# TSOC_GROVEY_ONE.net
KiCad netlist of a schematic drawn in EAGLE
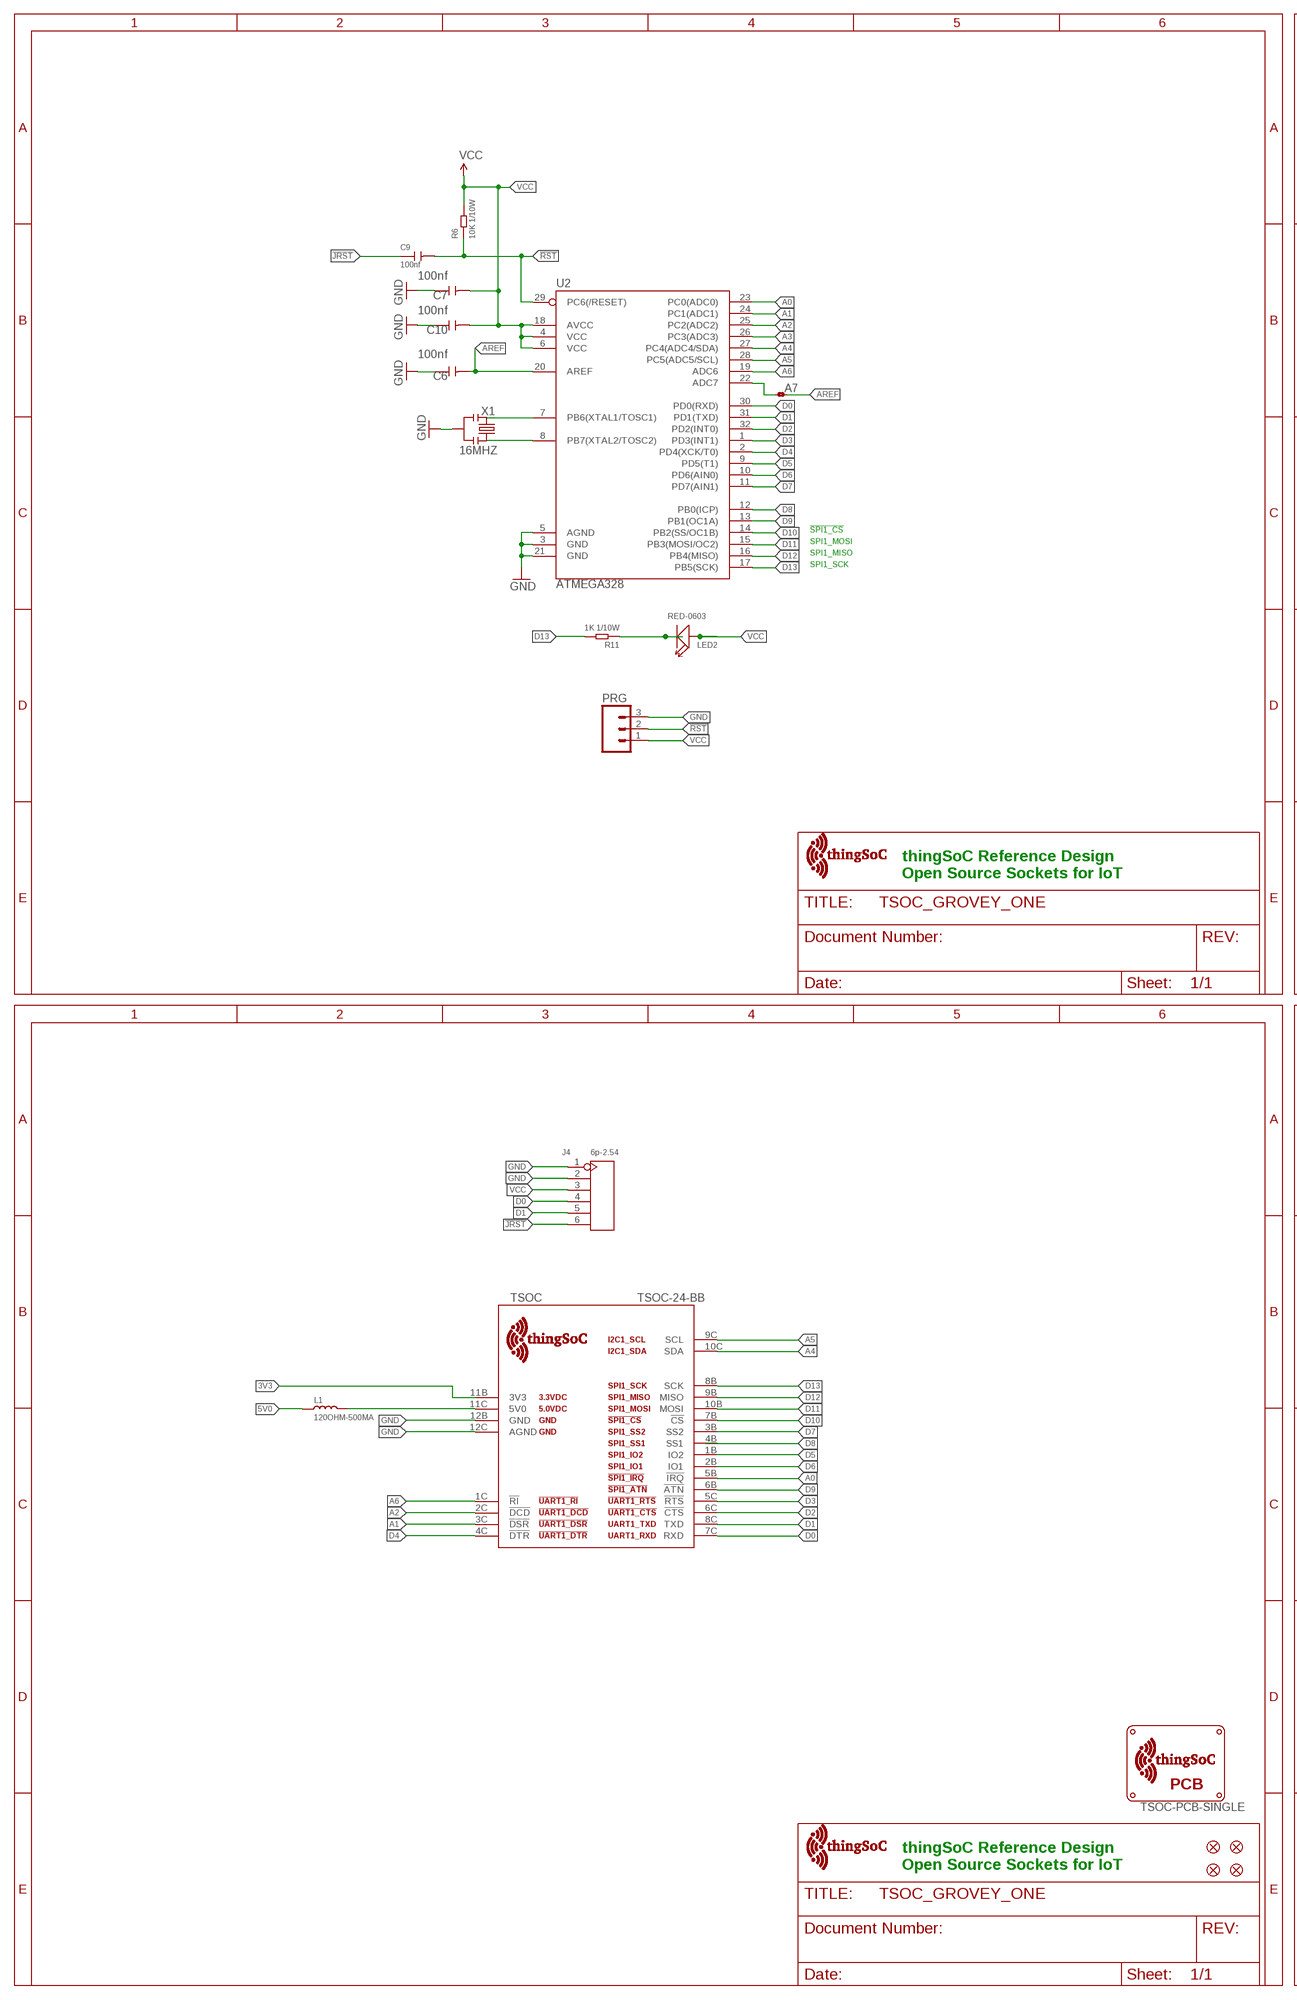
[diagram p0: schematic, sheet 1, part 1 of 2]
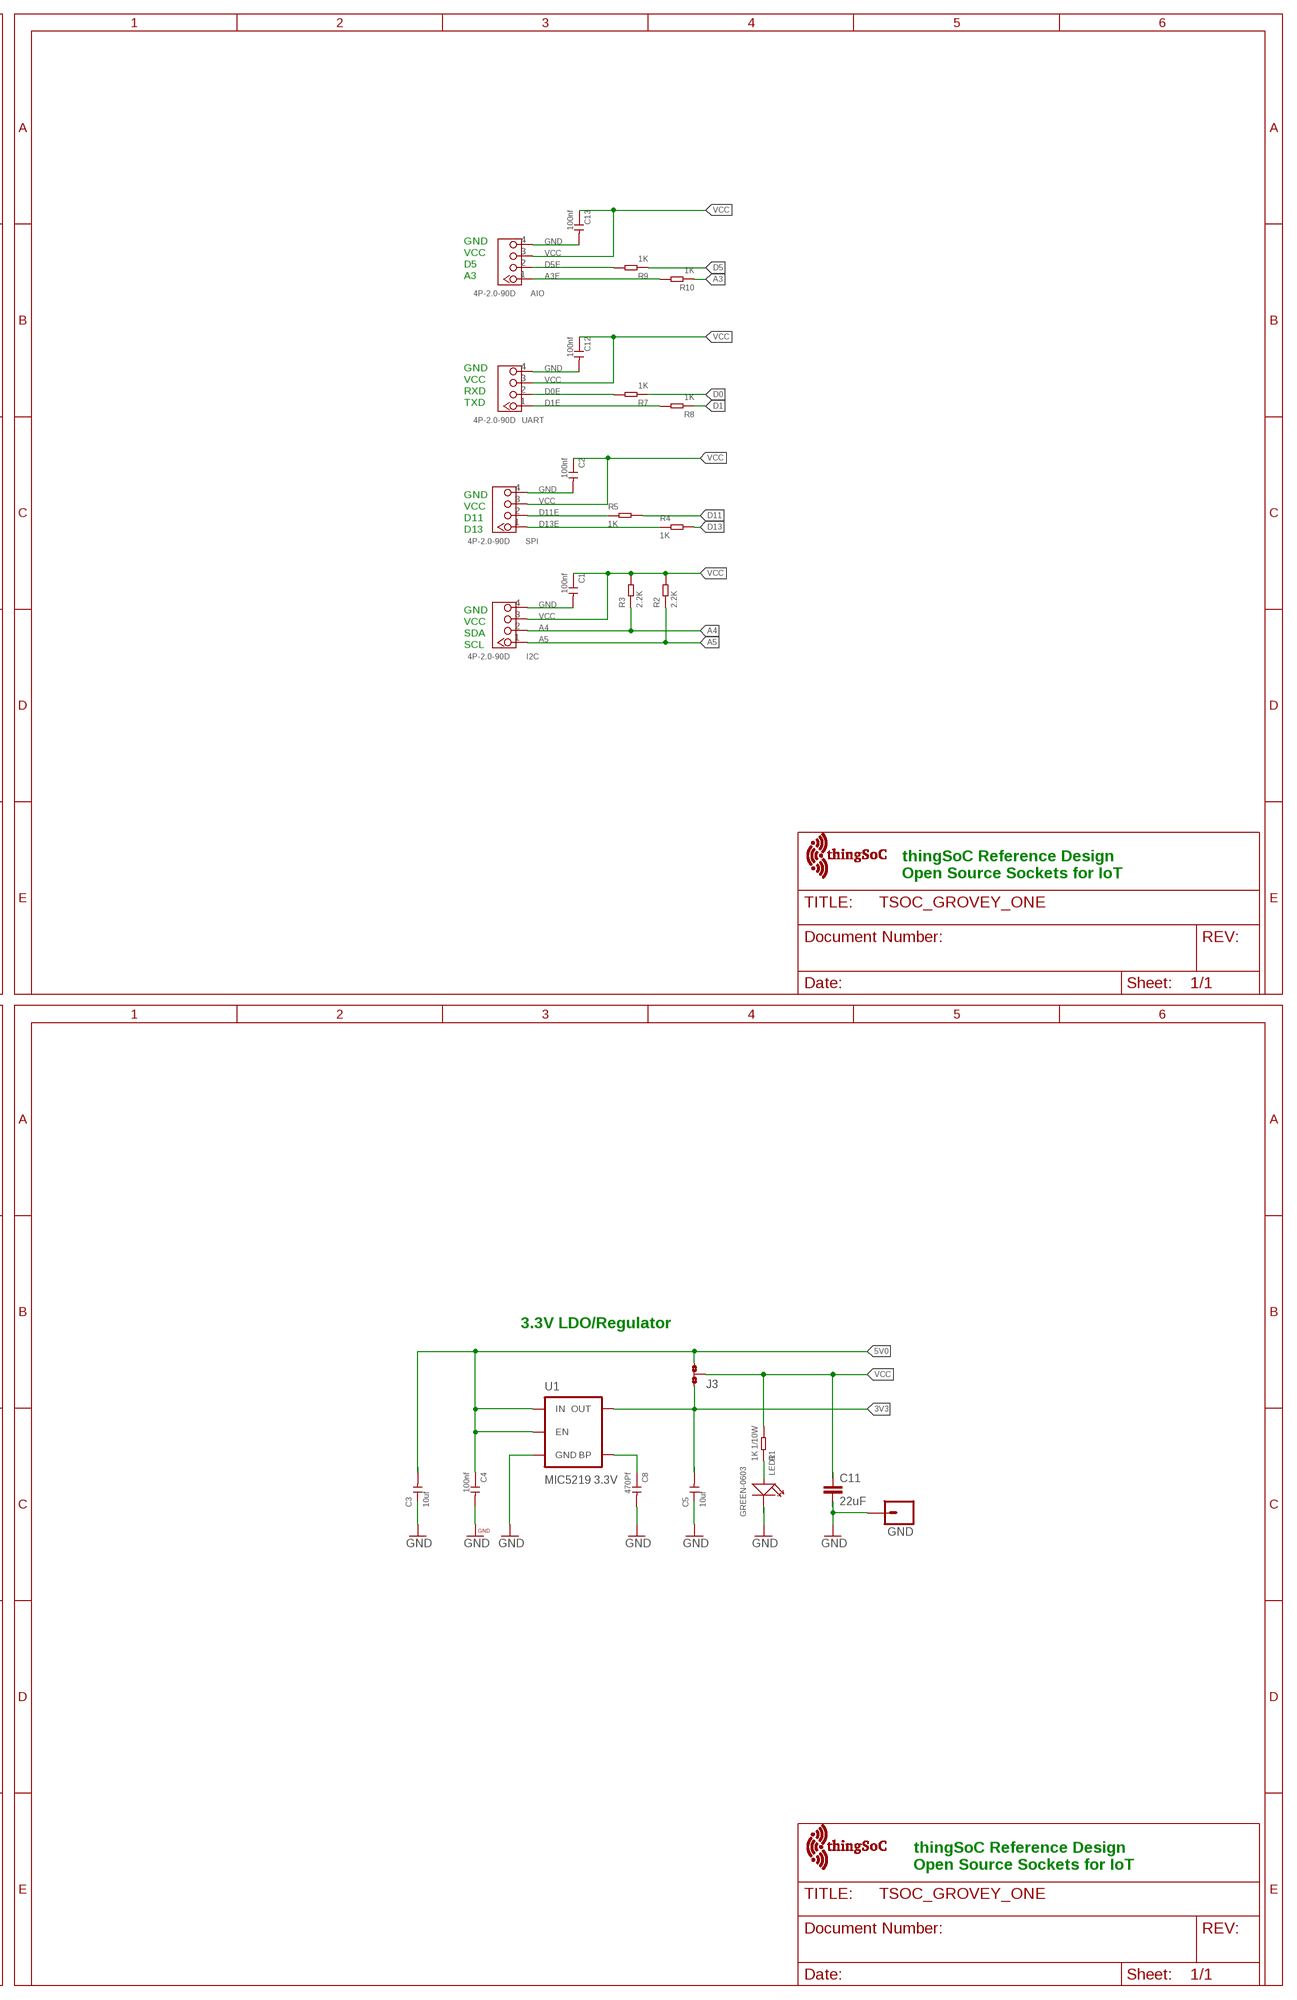
[diagram p1: schematic, sheet 1, part 2 of 2]

(export (version "E")
  (design (tool "Eeschema 10.0.6"))
  (components
    (comp (ref "$$U$1")
      (value "TSOC-PCB-SINGLE")
      (footprint "eagle-import:TSOC-BB-BRD-DIM")
      (libsource (lib "eagle-import") (part "TSOC-PCB-SINGLE"))
    )
    (comp (ref "A7")
      (value "JMP-2-NO")
      (footprint "eagle-import:JMP-2-NO")
      (libsource (lib "eagle-import") (part "JMP-2-NO"))
    )
    (comp (ref "AIO")
      (value "4P-2.0-90D")
      (footprint "eagle-import:HW4-2.0-90D")
      (libsource (lib "eagle-import") (part "GROVE-CONNECTOR-DIP-90D(4P-2.0)"))
    )
    (comp (ref "C1")
      (value "100nf")
      (footprint "eagle-import:C0603")
      (fields (field (name "MPN") "CC0603KRX7R9BB104"))
      (libsource (lib "eagle-import") (part "CERAMIC-100NF-50V-10%-X7R(0603)"))
    )
    (comp (ref "C2")
      (value "100nf")
      (footprint "eagle-import:C0603")
      (fields (field (name "MPN") "CC0603KRX7R9BB104"))
      (libsource (lib "eagle-import") (part "CERAMIC-100NF-50V-10%-X7R(0603)"))
    )
    (comp (ref "C3")
      (value "10uf")
      (footprint "eagle-import:C0603")
      (fields (field (name "MPN") "CC0603KRX5R6BB106"))
      (libsource (lib "eagle-import") (part "CERAMIC-10UF-10V-10%-X5R(0603)"))
    )
    (comp (ref "C4")
      (value "100nf")
      (footprint "eagle-import:C0603")
      (fields (field (name "MPN") "CC0603KRX7R9BB104"))
      (libsource (lib "eagle-import") (part "CERAMIC-100NF-50V-10%-X7R(0603)"))
    )
    (comp (ref "C5")
      (value "10uf")
      (footprint "eagle-import:C0603")
      (fields (field (name "MPN") "CC0603KRX5R6BB106"))
      (libsource (lib "eagle-import") (part "CERAMIC-10UF-10V-10%-X5R(0603)"))
    )
    (comp (ref "C6")
      (value "100nf")
      (footprint "eagle-import:C0603")
      (fields (field (name "MPN") "CC0603KRX7R9BB104"))
      (libsource (lib "eagle-import") (part "CERAMIC-100NF-50V-10%-X7R(0603)"))
    )
    (comp (ref "C7")
      (value "100nf")
      (footprint "eagle-import:C0603")
      (fields (field (name "MPN") "CC0603KRX7R9BB104"))
      (libsource (lib "eagle-import") (part "CERAMIC-100NF-50V-10%-X7R(0603)"))
    )
    (comp (ref "C8")
      (value "470Pf")
      (footprint "eagle-import:C0603")
      (fields (field (name "MPN") "CC0603KRX7R9BB104"))
      (libsource (lib "eagle-import") (part "CERAMIC-100NF-50V-10%-X7R(0603)"))
    )
    (comp (ref "C9")
      (value "100nf")
      (footprint "eagle-import:C0603")
      (fields (field (name "MPN") "CC0603KRX7R9BB104"))
      (libsource (lib "eagle-import") (part "CERAMIC-100NF-50V-10%-X7R(0603)"))
    )
    (comp (ref "C10")
      (value "100nf")
      (footprint "eagle-import:C0603")
      (fields (field (name "MPN") "CC0603KRX7R9BB104"))
      (libsource (lib "eagle-import") (part "CERAMIC-100NF-50V-10%-X7R(0603)"))
    )
    (comp (ref "C11")
      (value "22uF")
      (footprint "eagle-import:EIA-1206")
      (libsource (lib "eagle-import") (part "CAP-1206"))
    )
    (comp (ref "C12")
      (value "100nf")
      (footprint "eagle-import:C0603")
      (fields (field (name "MPN") "CC0603KRX7R9BB104"))
      (libsource (lib "eagle-import") (part "CERAMIC-100NF-50V-10%-X7R(0603)"))
    )
    (comp (ref "C13")
      (value "100nf")
      (footprint "eagle-import:C0603")
      (fields (field (name "MPN") "CC0603KRX7R9BB104"))
      (libsource (lib "eagle-import") (part "CERAMIC-100NF-50V-10%-X7R(0603)"))
    )
    (comp (ref "FID1")
      (value "FIDUCIALUFIDUCIAL")
      (footprint "eagle-import:MICRO-FIDUCIAL")
      (libsource (lib "eagle-import") (part "FIDUCIALUFIDUCIAL"))
    )
    (comp (ref "FID2")
      (value "FIDUCIALUFIDUCIAL")
      (footprint "eagle-import:MICRO-FIDUCIAL")
      (libsource (lib "eagle-import") (part "FIDUCIALUFIDUCIAL"))
    )
    (comp (ref "FID3")
      (value "FIDUCIALUFIDUCIAL")
      (footprint "eagle-import:MICRO-FIDUCIAL")
      (libsource (lib "eagle-import") (part "FIDUCIALUFIDUCIAL"))
    )
    (comp (ref "FID4")
      (value "FIDUCIALUFIDUCIAL")
      (footprint "eagle-import:MICRO-FIDUCIAL")
      (libsource (lib "eagle-import") (part "FIDUCIALUFIDUCIAL"))
    )
    (comp (ref "GND")
      (value "M01PTH")
      (footprint "eagle-import:1X01")
      (libsource (lib "eagle-import") (part "M01PTH"))
    )
    (comp (ref "I2C")
      (value "4P-2.0-90D")
      (footprint "eagle-import:HW4-2.0-90D")
      (libsource (lib "eagle-import") (part "GROVE-CONNECTOR-DIP-90D(4P-2.0)"))
    )
    (comp (ref "J3")
      (value "NO")
      (footprint "eagle-import:JMP-3-NO-PTH-2.54")
      (libsource (lib "eagle-import") (part "JMP-3-NO-PTH"))
    )
    (comp (ref "J4")
      (value "6p-2.54")
      (footprint "eagle-import:H6-2.54")
      (fields (field (name "MPN") "P125-1106A1BS116A1"))
      (libsource (lib "eagle-import") (part "DIP-BLACK-MALE-HEADER(6P-2.54)"))
    )
    (comp (ref "L1")
      (value "120OHM-500MA")
      (footprint "eagle-import:L0603")
      (fields (field (name "MPN") "BLM18AG121SN1D"))
      (libsource (lib "eagle-import") (part "SMD-FERRITE-CHIP-120-OHM-500MA(0603)"))
    )
    (comp (ref "LED1")
      (value "GREEN-0603")
      (footprint "eagle-import:LED-0603")
      (fields (field (name "MPN") "19-217-G7C-AN1P2-3T"))
      (libsource (lib "eagle-import") (part "SMD-LED-CLEAR-GREEN(0603)"))
    )
    (comp (ref "LED2")
      (value "RED-0603")
      (footprint "eagle-import:LED-0603")
      (fields (field (name "MPN") "19-217-G7C-AN1P2-3T"))
      (libsource (lib "eagle-import") (part "SMD-LED-CLEAR-GREEN(0603)"))
    )
    (comp (ref "PRG")
      (value "M03PTH")
      (footprint "eagle-import:1X03")
      (libsource (lib "eagle-import") (part "M03PTH"))
    )
    (comp (ref "R1")
      (value "1K 1/10W")
      (footprint "eagle-import:R0603")
      (fields (field (name "MPN") "RC0603JR-071KL"))
      (libsource (lib "eagle-import") (part "SMD-RES-1K-5%-1/10W(0603)"))
    )
    (comp (ref "R2")
      (value "2.2K")
      (footprint "eagle-import:R0603")
      (fields (field (name "MPN") "RC0603JR-072K2L"))
      (libsource (lib "eagle-import") (part "SMD-RES-2.2K-5%-1/10W(0603)"))
    )
    (comp (ref "R3")
      (value "2.2K")
      (footprint "eagle-import:R0603")
      (fields (field (name "MPN") "RC0603JR-072K2L"))
      (libsource (lib "eagle-import") (part "SMD-RES-2.2K-5%-1/10W(0603)"))
    )
    (comp (ref "R4")
      (value "1K")
      (footprint "eagle-import:R0603")
      (fields (field (name "MPN") "RC0603JR-072K2L"))
      (libsource (lib "eagle-import") (part "SMD-RES-2.2K-5%-1/10W(0603)"))
    )
    (comp (ref "R5")
      (value "1K")
      (footprint "eagle-import:R0603")
      (fields (field (name "MPN") "RC0603JR-072K2L"))
      (libsource (lib "eagle-import") (part "SMD-RES-2.2K-5%-1/10W(0603)"))
    )
    (comp (ref "R6")
      (value "10K 1/10W")
      (footprint "eagle-import:R0603")
      (fields (field (name "MPN") "RC0603JR-0710KL"))
      (libsource (lib "eagle-import") (part "SMD-RES-10K-5%-1/10W(0603)"))
    )
    (comp (ref "R7")
      (value "1K")
      (footprint "eagle-import:R0603")
      (fields (field (name "MPN") "RC0603JR-072K2L"))
      (libsource (lib "eagle-import") (part "SMD-RES-2.2K-5%-1/10W(0603)"))
    )
    (comp (ref "R8")
      (value "1K")
      (footprint "eagle-import:R0603")
      (fields (field (name "MPN") "RC0603JR-072K2L"))
      (libsource (lib "eagle-import") (part "SMD-RES-2.2K-5%-1/10W(0603)"))
    )
    (comp (ref "R9")
      (value "1K")
      (footprint "eagle-import:R0603")
      (fields (field (name "MPN") "RC0603JR-072K2L"))
      (libsource (lib "eagle-import") (part "SMD-RES-2.2K-5%-1/10W(0603)"))
    )
    (comp (ref "R10")
      (value "1K")
      (footprint "eagle-import:R0603")
      (fields (field (name "MPN") "RC0603JR-072K2L"))
      (libsource (lib "eagle-import") (part "SMD-RES-2.2K-5%-1/10W(0603)"))
    )
    (comp (ref "R11")
      (value "1K 1/10W")
      (footprint "eagle-import:R0603")
      (fields (field (name "MPN") "RC0603JR-071KL"))
      (libsource (lib "eagle-import") (part "SMD-RES-1K-5%-1/10W(0603)"))
    )
    (comp (ref "SPI")
      (value "4P-2.0-90D")
      (footprint "eagle-import:HW4-2.0-90D")
      (libsource (lib "eagle-import") (part "GROVE-CONNECTOR-DIP-90D(4P-2.0)"))
    )
    (comp (ref "TSOC")
      (value "TSOC-24-BB")
      (footprint "eagle-import:TSOC-BB-S24")
      (libsource (lib "eagle-import") (part "TSOC-24-BB"))
    )
    (comp (ref "U$1")
      (value "TSOC-LOGO-SMALL")
      (footprint "eagle-import:TSOC-LOGO-SML")
      (libsource (lib "eagle-import") (part "TSOC-LOGO-SMALL"))
    )
    (comp (ref "U$101")
      (value "TSOC-LOGO-SMALL")
      (footprint "eagle-import:TSOC-LOGO-SML")
      (libsource (lib "eagle-import") (part "TSOC-LOGO-SMALL"))
    )
    (comp (ref "U$102")
      (value "TSOC-LOGO-LRG")
      (footprint "eagle-import:TSOC-LOGO-LRG")
      (libsource (lib "eagle-import") (part "TSOC-LOGO-LRG"))
    )
    (comp (ref "U$103")
      (value "TSOC-LOGO-SMALL")
      (footprint "eagle-import:TSOC-LOGO-SML")
      (libsource (lib "eagle-import") (part "TSOC-LOGO-SMALL"))
    )
    (comp (ref "U1")
      (value "MIC5219 3.3V")
      (footprint "eagle-import:SOT23-5")
      (libsource (lib "eagle-import") (part "V_REG_MIC52193.3V"))
    )
    (comp (ref "U2")
      (value "ATMEGA328")
      (footprint "eagle-import:TQFP32-08")
      (libsource (lib "eagle-import") (part "ATMEGA168"))
    )
    (comp (ref "UART")
      (value "4P-2.0-90D")
      (footprint "eagle-import:HW4-2.0-90D")
      (libsource (lib "eagle-import") (part "GROVE-CONNECTOR-DIP-90D(4P-2.0)"))
    )
    (comp (ref "X1")
      (value "16MHZ")
      (footprint "eagle-import:X3-SMD-3.6X1.3X0.8MM")
      (fields (field (name "MPN") "CSTCE16M0V53-R0"))
      (libsource (lib "eagle-import") (part "SMD-RESONATOR-16MHZ-15PF-0.5%-40R(3P-3.2X1.3MM)"))
    )
  )
  (nets
    (net (code "1") (name "/A3E") (class "Default")
      (node (ref "AIO") (pin "1") (pinfunction "1_1") (pintype "bidirectional"))
      (node (ref "R10") (pin "2") (pinfunction "2_2") (pintype "passive"))
    )
    (net (code "2") (name "/D0E") (class "Default")
      (node (ref "R7") (pin "2") (pinfunction "2_2") (pintype "passive"))
      (node (ref "UART") (pin "2") (pinfunction "2_2") (pintype "bidirectional"))
    )
    (net (code "3") (name "/D1E") (class "Default")
      (node (ref "R8") (pin "2") (pinfunction "2_2") (pintype "passive"))
      (node (ref "UART") (pin "1") (pinfunction "1_1") (pintype "bidirectional"))
    )
    (net (code "4") (name "/D5E") (class "Default")
      (node (ref "AIO") (pin "2") (pinfunction "2_2") (pintype "bidirectional"))
      (node (ref "R9") (pin "2") (pinfunction "2_2") (pintype "passive"))
    )
    (net (code "5") (name "/D11E") (class "Default")
      (node (ref "R5") (pin "1") (pinfunction "1_1") (pintype "passive"))
      (node (ref "SPI") (pin "2") (pinfunction "2_2") (pintype "bidirectional"))
    )
    (net (code "6") (name "/D13E") (class "Default")
      (node (ref "R4") (pin "1") (pinfunction "1_1") (pintype "passive"))
      (node (ref "SPI") (pin "1") (pinfunction "1_1") (pintype "bidirectional"))
    )
    (net (code "7") (name "/~{JRST}") (class "Default")
      (node (ref "C9") (pin "1") (pinfunction "1_1") (pintype "passive"))
      (node (ref "J4") (pin "6") (pinfunction "6_6") (pintype "bidirectional"))
    )
    (net (code "8") (name "/~{RST}") (class "Default")
      (node (ref "C9") (pin "2") (pinfunction "2_2") (pintype "passive"))
      (node (ref "PRG") (pin "2") (pinfunction "2_2") (pintype "passive"))
      (node (ref "R6") (pin "1") (pinfunction "1_1") (pintype "passive"))
      (node (ref "U2") (pin "29") (pinfunction "PC6(/RESET)_29") (pintype "bidirectional"))
    )
    (net (code "9") (name "3V3") (class "Default")
      (node (ref "C5") (pin "2") (pinfunction "2_2") (pintype "passive"))
      (node (ref "J3") (pin "1") (pinfunction "1_1") (pintype "passive"))
      (node (ref "TSOC") (pin "11B") (pinfunction "3V3_11B") (pintype "bidirectional"))
      (node (ref "U1") (pin "5") (pinfunction "OUT_5") (pintype "passive"))
    )
    (net (code "10") (name "5V0") (class "Default")
      (node (ref "C3") (pin "2") (pinfunction "2_2") (pintype "passive"))
      (node (ref "C4") (pin "1") (pinfunction "1_1") (pintype "passive"))
      (node (ref "J3") (pin "3") (pinfunction "3_3") (pintype "passive"))
      (node (ref "L1") (pin "1") (pinfunction "1_1") (pintype "passive"))
      (node (ref "U1") (pin "1") (pinfunction "IN_1") (pintype "input"))
      (node (ref "U1") (pin "3") (pinfunction "EN_3") (pintype "input"))
    )
    (net (code "11") (name "A0") (class "Default")
      (node (ref "TSOC") (pin "5B") (pinfunction "~{IRQ}_5B") (pintype "bidirectional"))
      (node (ref "U2") (pin "23") (pinfunction "PC0(ADC0)_23") (pintype "bidirectional"))
    )
    (net (code "12") (name "A1") (class "Default")
      (node (ref "TSOC") (pin "3C") (pinfunction "~{DSR}_3C") (pintype "bidirectional"))
      (node (ref "U2") (pin "24") (pinfunction "PC1(ADC1)_24") (pintype "bidirectional"))
    )
    (net (code "13") (name "A2") (class "Default")
      (node (ref "TSOC") (pin "2C") (pinfunction "~{DCD}_2C") (pintype "bidirectional"))
      (node (ref "U2") (pin "25") (pinfunction "PC2(ADC2)_25") (pintype "bidirectional"))
    )
    (net (code "14") (name "A3") (class "Default")
      (node (ref "R10") (pin "1") (pinfunction "1_1") (pintype "passive"))
      (node (ref "U2") (pin "26") (pinfunction "PC3(ADC3)_26") (pintype "bidirectional"))
    )
    (net (code "15") (name "A4") (class "Default")
      (node (ref "I2C") (pin "2") (pinfunction "2_2") (pintype "bidirectional"))
      (node (ref "R3") (pin "1") (pinfunction "1_1") (pintype "passive"))
      (node (ref "TSOC") (pin "10C") (pinfunction "SDA_10C") (pintype "bidirectional"))
      (node (ref "U2") (pin "27") (pinfunction "PC4(ADC4/SDA)_27") (pintype "bidirectional"))
    )
    (net (code "16") (name "A5") (class "Default")
      (node (ref "I2C") (pin "1") (pinfunction "1_1") (pintype "bidirectional"))
      (node (ref "R2") (pin "1") (pinfunction "1_1") (pintype "passive"))
      (node (ref "TSOC") (pin "9C") (pinfunction "SCL_9C") (pintype "bidirectional"))
      (node (ref "U2") (pin "28") (pinfunction "PC5(ADC5/SCL)_28") (pintype "bidirectional"))
    )
    (net (code "17") (name "A6") (class "Default")
      (node (ref "TSOC") (pin "1C") (pinfunction "~{RI}_1C") (pintype "bidirectional"))
      (node (ref "U2") (pin "19") (pinfunction "ADC6_19") (pintype "bidirectional"))
    )
    (net (code "18") (name "AREF") (class "Default")
      (node (ref "A7") (pin "2") (pinfunction "2_2") (pintype "passive"))
      (node (ref "C6") (pin "2") (pinfunction "2_2") (pintype "passive"))
      (node (ref "U2") (pin "20") (pinfunction "AREF_20") (pintype "bidirectional"))
    )
    (net (code "19") (name "D0") (class "Default")
      (node (ref "J4") (pin "4") (pinfunction "4_4") (pintype "bidirectional"))
      (node (ref "R7") (pin "1") (pinfunction "1_1") (pintype "passive"))
      (node (ref "TSOC") (pin "7C") (pinfunction "RXD_7C") (pintype "bidirectional"))
      (node (ref "U2") (pin "30") (pinfunction "PD0(RXD)_30") (pintype "bidirectional"))
    )
    (net (code "20") (name "D1") (class "Default")
      (node (ref "J4") (pin "5") (pinfunction "5_5") (pintype "bidirectional"))
      (node (ref "R8") (pin "1") (pinfunction "1_1") (pintype "passive"))
      (node (ref "TSOC") (pin "8C") (pinfunction "TXD_8C") (pintype "bidirectional"))
      (node (ref "U2") (pin "31") (pinfunction "PD1(TXD)_31") (pintype "bidirectional"))
    )
    (net (code "21") (name "D2") (class "Default")
      (node (ref "TSOC") (pin "6C") (pinfunction "~{CTS}_6C") (pintype "bidirectional"))
      (node (ref "U2") (pin "32") (pinfunction "PD2(INT0)_32") (pintype "bidirectional"))
    )
    (net (code "22") (name "D3") (class "Default")
      (node (ref "TSOC") (pin "5C") (pinfunction "~{RTS}_5C") (pintype "bidirectional"))
      (node (ref "U2") (pin "1") (pinfunction "PD3(INT1)_1") (pintype "bidirectional"))
    )
    (net (code "23") (name "D4") (class "Default")
      (node (ref "TSOC") (pin "4C") (pinfunction "~{DTR}_4C") (pintype "bidirectional"))
      (node (ref "U2") (pin "2") (pinfunction "PD4(XCK/T0)_2") (pintype "bidirectional"))
    )
    (net (code "24") (name "D5") (class "Default")
      (node (ref "R9") (pin "1") (pinfunction "1_1") (pintype "passive"))
      (node (ref "TSOC") (pin "1B") (pinfunction "IO2_1B") (pintype "bidirectional"))
      (node (ref "U2") (pin "9") (pinfunction "PD5(T1)_9") (pintype "bidirectional"))
    )
    (net (code "25") (name "D6") (class "Default")
      (node (ref "TSOC") (pin "2B") (pinfunction "IO1_2B") (pintype "bidirectional"))
      (node (ref "U2") (pin "10") (pinfunction "PD6(AIN0)_10") (pintype "bidirectional"))
    )
    (net (code "26") (name "D7") (class "Default")
      (node (ref "TSOC") (pin "3B") (pinfunction "SS2_3B") (pintype "bidirectional"))
      (node (ref "U2") (pin "11") (pinfunction "PD7(AIN1)_11") (pintype "bidirectional"))
    )
    (net (code "27") (name "D8") (class "Default")
      (node (ref "TSOC") (pin "4B") (pinfunction "SS1_4B") (pintype "bidirectional"))
      (node (ref "U2") (pin "12") (pinfunction "PB0(ICP)_12") (pintype "bidirectional"))
    )
    (net (code "28") (name "D9") (class "Default")
      (node (ref "TSOC") (pin "6B") (pinfunction "~{ATN}_6B") (pintype "bidirectional"))
      (node (ref "U2") (pin "13") (pinfunction "PB1(OC1A)_13") (pintype "bidirectional"))
    )
    (net (code "29") (name "D10") (class "Default")
      (node (ref "TSOC") (pin "7B") (pinfunction "~{CS}_7B") (pintype "bidirectional"))
      (node (ref "U2") (pin "14") (pinfunction "PB2(SS/OC1B)_14") (pintype "bidirectional"))
    )
    (net (code "30") (name "D11") (class "Default")
      (node (ref "R5") (pin "2") (pinfunction "2_2") (pintype "passive"))
      (node (ref "TSOC") (pin "10B") (pinfunction "MOSI_10B") (pintype "bidirectional"))
      (node (ref "U2") (pin "15") (pinfunction "PB3(MOSI/OC2)_15") (pintype "bidirectional"))
    )
    (net (code "31") (name "D12") (class "Default")
      (node (ref "TSOC") (pin "9B") (pinfunction "MISO_9B") (pintype "bidirectional"))
      (node (ref "U2") (pin "16") (pinfunction "PB4(MISO)_16") (pintype "bidirectional"))
    )
    (net (code "32") (name "D13") (class "Default")
      (node (ref "R11") (pin "2") (pinfunction "2_2") (pintype "passive"))
      (node (ref "R4") (pin "2") (pinfunction "2_2") (pintype "passive"))
      (node (ref "TSOC") (pin "8B") (pinfunction "SCK_8B") (pintype "bidirectional"))
      (node (ref "U2") (pin "17") (pinfunction "PB5(SCK)_17") (pintype "bidirectional"))
    )
    (net (code "33") (name "GND") (class "Default")
      (node (ref "AIO") (pin "4") (pinfunction "4_4") (pintype "bidirectional"))
      (node (ref "C1") (pin "2") (pinfunction "2_2") (pintype "passive"))
      (node (ref "C10") (pin "1") (pinfunction "1_1") (pintype "passive"))
      (node (ref "C11") (pin "2") (pinfunction "2_2") (pintype "passive"))
      (node (ref "C12") (pin "2") (pinfunction "2_2") (pintype "passive"))
      (node (ref "C13") (pin "2") (pinfunction "2_2") (pintype "passive"))
      (node (ref "C2") (pin "2") (pinfunction "2_2") (pintype "passive"))
      (node (ref "C3") (pin "1") (pinfunction "1_1") (pintype "passive"))
      (node (ref "C4") (pin "2") (pinfunction "2_2") (pintype "passive"))
      (node (ref "C5") (pin "1") (pinfunction "1_1") (pintype "passive"))
      (node (ref "C6") (pin "1") (pinfunction "1_1") (pintype "passive"))
      (node (ref "C7") (pin "1") (pinfunction "1_1") (pintype "passive"))
      (node (ref "C8") (pin "2") (pinfunction "2_2") (pintype "passive"))
      (node (ref "GND") (pin "1") (pinfunction "1_1") (pintype "passive"))
      (node (ref "I2C") (pin "4") (pinfunction "4_4") (pintype "bidirectional"))
      (node (ref "J4") (pin "1") (pinfunction "1_1") (pintype "bidirectional"))
      (node (ref "J4") (pin "2") (pinfunction "2_2") (pintype "bidirectional"))
      (node (ref "LED1") (pin "-") (pinfunction "-_-") (pintype "passive"))
      (node (ref "PRG") (pin "3") (pinfunction "3_3") (pintype "passive"))
      (node (ref "SPI") (pin "4") (pinfunction "4_4") (pintype "bidirectional"))
      (node (ref "TSOC") (pin "12B") (pinfunction "GND_12B") (pintype "bidirectional"))
      (node (ref "TSOC") (pin "12C") (pinfunction "AGND_12C") (pintype "bidirectional"))
      (node (ref "U1") (pin "2") (pinfunction "GND_2") (pintype "input"))
      (node (ref "U2") (pin "21") (pinfunction "GND_21") (pintype "bidirectional"))
      (node (ref "U2") (pin "3") (pinfunction "GND_3") (pintype "bidirectional"))
      (node (ref "U2") (pin "5") (pinfunction "AGND_5") (pintype "bidirectional"))
      (node (ref "UART") (pin "4") (pinfunction "4_4") (pintype "bidirectional"))
      (node (ref "X1") (pin "2") (pinfunction "2_2") (pintype "passive"))
    )
    (net (code "34") (name "Net-(LED1-Pad+)") (class "Default")
      (node (ref "LED1") (pin "+") (pinfunction "+_+") (pintype "passive"))
      (node (ref "R1") (pin "1") (pinfunction "1_1") (pintype "passive"))
    )
    (net (code "35") (name "Net-(LED2-Pad-)") (class "Default")
      (node (ref "LED2") (pin "-") (pinfunction "-_-") (pintype "passive"))
      (node (ref "R11") (pin "1") (pinfunction "1_1") (pintype "passive"))
    )
    (net (code "36") (name "Net-(TSOC-5V0)") (class "Default")
      (node (ref "L1") (pin "2") (pinfunction "2_2") (pintype "passive"))
      (node (ref "TSOC") (pin "11C") (pinfunction "5V0_11C") (pintype "bidirectional"))
    )
    (net (code "37") (name "Net-(U1-BP)") (class "Default")
      (node (ref "C8") (pin "1") (pinfunction "1_1") (pintype "passive"))
      (node (ref "U1") (pin "4") (pinfunction "BP_4") (pintype "input"))
    )
    (net (code "38") (name "Net-(U2-ADC7)") (class "Default")
      (node (ref "A7") (pin "1") (pinfunction "1_1") (pintype "passive"))
      (node (ref "U2") (pin "22") (pinfunction "ADC7_22") (pintype "bidirectional"))
    )
    (net (code "39") (name "Net-(U2-PB6(XTAL1{slash}TOSC1))") (class "Default")
      (node (ref "U2") (pin "7") (pinfunction "PB6(XTAL1/TOSC1)_7") (pintype "bidirectional"))
      (node (ref "X1") (pin "3") (pinfunction "3_3") (pintype "passive"))
    )
    (net (code "40") (name "Net-(U2-PB7(XTAL2{slash}TOSC2))") (class "Default")
      (node (ref "U2") (pin "8") (pinfunction "PB7(XTAL2/TOSC2)_8") (pintype "bidirectional"))
      (node (ref "X1") (pin "1") (pinfunction "1_1") (pintype "passive"))
    )
    (net (code "41") (name "VCC") (class "Default")
      (node (ref "AIO") (pin "3") (pinfunction "3_3") (pintype "bidirectional"))
      (node (ref "C1") (pin "1") (pinfunction "1_1") (pintype "passive"))
      (node (ref "C10") (pin "2") (pinfunction "2_2") (pintype "passive"))
      (node (ref "C11") (pin "1") (pinfunction "1_1") (pintype "passive"))
      (node (ref "C12") (pin "1") (pinfunction "1_1") (pintype "passive"))
      (node (ref "C13") (pin "1") (pinfunction "1_1") (pintype "passive"))
      (node (ref "C2") (pin "1") (pinfunction "1_1") (pintype "passive"))
      (node (ref "C7") (pin "2") (pinfunction "2_2") (pintype "passive"))
      (node (ref "I2C") (pin "3") (pinfunction "3_3") (pintype "bidirectional"))
      (node (ref "J3") (pin "2") (pinfunction "2_2") (pintype "passive"))
      (node (ref "J4") (pin "3") (pinfunction "3_3") (pintype "bidirectional"))
      (node (ref "LED2") (pin "+") (pinfunction "+_+") (pintype "passive"))
      (node (ref "PRG") (pin "1") (pinfunction "1_1") (pintype "passive"))
      (node (ref "R1") (pin "2") (pinfunction "2_2") (pintype "passive"))
      (node (ref "R2") (pin "2") (pinfunction "2_2") (pintype "passive"))
      (node (ref "R3") (pin "2") (pinfunction "2_2") (pintype "passive"))
      (node (ref "R6") (pin "2") (pinfunction "2_2") (pintype "passive"))
      (node (ref "SPI") (pin "3") (pinfunction "3_3") (pintype "bidirectional"))
      (node (ref "U2") (pin "18") (pinfunction "AVCC_18") (pintype "bidirectional"))
      (node (ref "U2") (pin "4") (pinfunction "VCC_4") (pintype "bidirectional"))
      (node (ref "U2") (pin "6") (pinfunction "VCC_6") (pintype "bidirectional"))
      (node (ref "UART") (pin "3") (pinfunction "3_3") (pintype "bidirectional"))
    )
  )
)
